# 04B-005.net
KiCad netlist of a schematic drawn in EAGLE
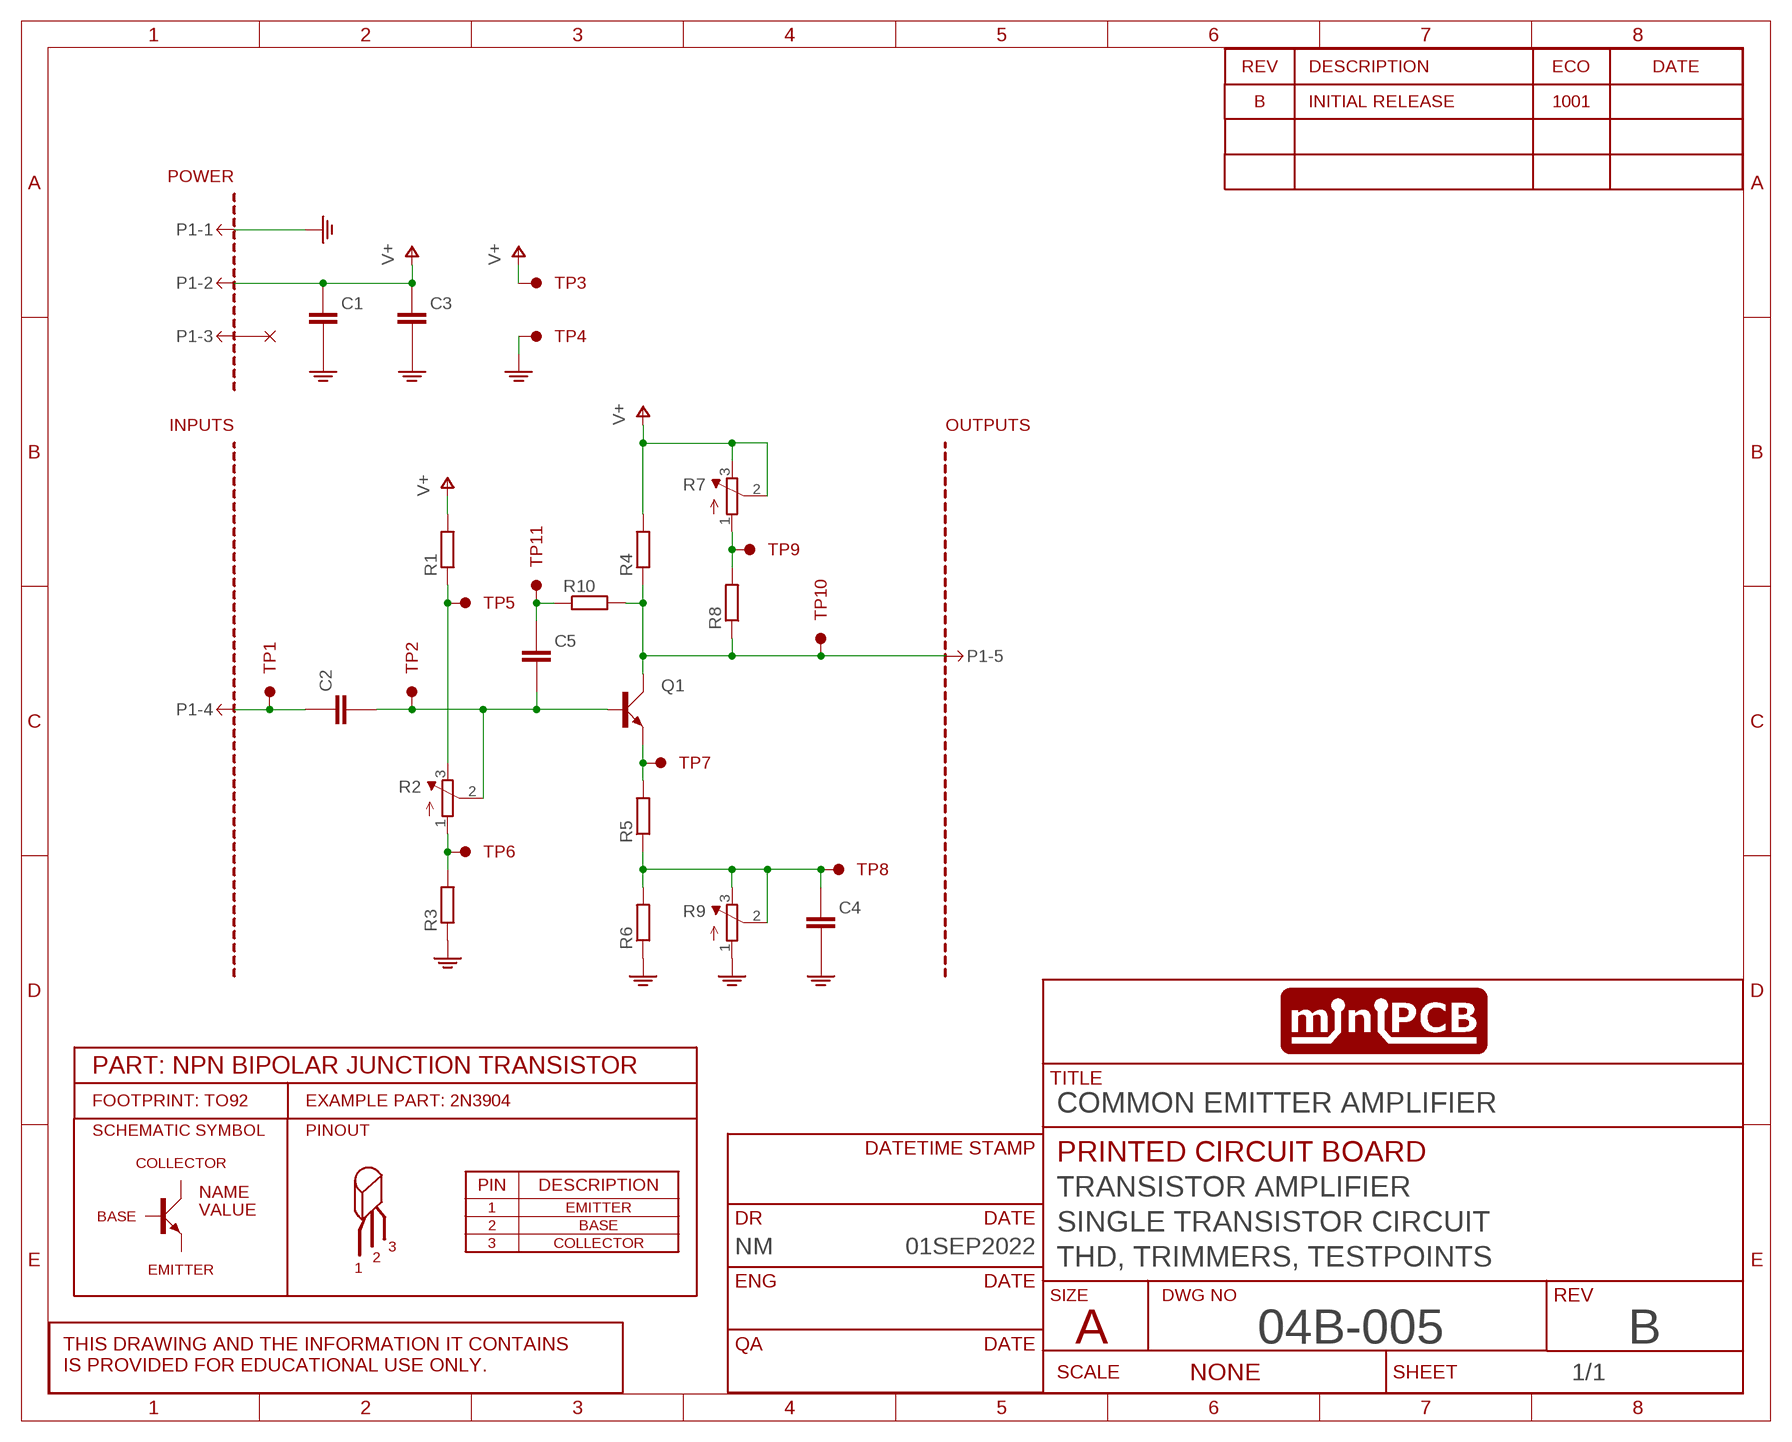
[diagram p0: schematic, sheet 1]

(export (version "E")
  (design (tool "Eeschema 10.0.6"))
  (components
    (comp (ref "C1")
      (value "CAPACITORTHD")
      (footprint "eagle-import:C050-024X044")
      (libsource (lib "eagle-import") (part "CAPACITORTHD"))
    )
    (comp (ref "C2")
      (value "CAPACITORTHD")
      (footprint "eagle-import:C050-024X044")
      (libsource (lib "eagle-import") (part "CAPACITORTHD"))
    )
    (comp (ref "C3")
      (value "CAPACITORTHD")
      (footprint "eagle-import:C050-024X044")
      (libsource (lib "eagle-import") (part "CAPACITORTHD"))
    )
    (comp (ref "C4")
      (value "CAPACITORTHD")
      (footprint "eagle-import:C050-024X044")
      (libsource (lib "eagle-import") (part "CAPACITORTHD"))
    )
    (comp (ref "C5")
      (value "CAPACITORTHD")
      (footprint "eagle-import:C050-024X044")
      (libsource (lib "eagle-import") (part "CAPACITORTHD"))
    )
    (comp (ref "P1-")
      (value "MINIPCB_5P50X50")
      (footprint "eagle-import:MINIPCB_5P_50X50MM")
      (fields (field (name "PART_NUMBER") "X04B-005-B"))
      (libsource (lib "eagle-import") (part "MINIPCB_5P50X50"))
    )
    (comp (ref "Q1")
      (value "BJT_NPNEBC")
      (footprint "eagle-import:TO92-EBC-OVAL")
      (libsource (lib "eagle-import") (part "BJT_NPNEBC"))
    )
    (comp (ref "R1")
      (value "RESISTOR10MM")
      (footprint "eagle-import:0207_10")
      (libsource (lib "eagle-import") (part "RESISTOR10MM"))
    )
    (comp (ref "R2")
      (value "TRIMPOT0.100THD")
      (footprint "eagle-import:TRIM_0100")
      (libsource (lib "eagle-import") (part "TRIMPOT0.100THD"))
    )
    (comp (ref "R3")
      (value "RESISTOR10MM")
      (footprint "eagle-import:0207_10")
      (libsource (lib "eagle-import") (part "RESISTOR10MM"))
    )
    (comp (ref "R4")
      (value "RESISTOR10MM")
      (footprint "eagle-import:0207_10")
      (libsource (lib "eagle-import") (part "RESISTOR10MM"))
    )
    (comp (ref "R5")
      (value "RESISTOR10MM")
      (footprint "eagle-import:0207_10")
      (libsource (lib "eagle-import") (part "RESISTOR10MM"))
    )
    (comp (ref "R6")
      (value "RESISTOR10MM")
      (footprint "eagle-import:0207_10")
      (libsource (lib "eagle-import") (part "RESISTOR10MM"))
    )
    (comp (ref "R7")
      (value "TRIMPOT0.100THD")
      (footprint "eagle-import:TRIM_0100")
      (libsource (lib "eagle-import") (part "TRIMPOT0.100THD"))
    )
    (comp (ref "R8")
      (value "RESISTOR10MM")
      (footprint "eagle-import:0207_10")
      (libsource (lib "eagle-import") (part "RESISTOR10MM"))
    )
    (comp (ref "R9")
      (value "TRIMPOT0.100THD")
      (footprint "eagle-import:TRIM_0100")
      (libsource (lib "eagle-import") (part "TRIMPOT0.100THD"))
    )
    (comp (ref "R10")
      (value "RESISTOR10MM")
      (footprint "eagle-import:0207_10")
      (libsource (lib "eagle-import") (part "RESISTOR10MM"))
    )
    (comp (ref "TP1")
      (value "TESTPOINTKE5000-SMTEXT")
      (footprint "eagle-import:PINS_1_TESTPOINT_KE5000_NOTEXT")
      (libsource (lib "eagle-import") (part "TESTPOINTKE5000-SMTEXT"))
    )
    (comp (ref "TP2")
      (value "TESTPOINTKE5000-SMTEXT")
      (footprint "eagle-import:PINS_1_TESTPOINT_KE5000_NOTEXT")
      (libsource (lib "eagle-import") (part "TESTPOINTKE5000-SMTEXT"))
    )
    (comp (ref "TP3")
      (value "TESTPOINTKE5000-SMTEXT")
      (footprint "eagle-import:PINS_1_TESTPOINT_KE5000_NOTEXT")
      (libsource (lib "eagle-import") (part "TESTPOINTKE5000-SMTEXT"))
    )
    (comp (ref "TP4")
      (value "TESTPOINTKE5000-SMTEXT")
      (footprint "eagle-import:PINS_1_TESTPOINT_KE5000_NOTEXT")
      (libsource (lib "eagle-import") (part "TESTPOINTKE5000-SMTEXT"))
    )
    (comp (ref "TP5")
      (value "TESTPOINTKE5000-SMTEXT")
      (footprint "eagle-import:PINS_1_TESTPOINT_KE5000_NOTEXT")
      (libsource (lib "eagle-import") (part "TESTPOINTKE5000-SMTEXT"))
    )
    (comp (ref "TP6")
      (value "TESTPOINTKE5000-SMTEXT")
      (footprint "eagle-import:PINS_1_TESTPOINT_KE5000_NOTEXT")
      (libsource (lib "eagle-import") (part "TESTPOINTKE5000-SMTEXT"))
    )
    (comp (ref "TP7")
      (value "TESTPOINTKE5000-SMTEXT")
      (footprint "eagle-import:PINS_1_TESTPOINT_KE5000_NOTEXT")
      (libsource (lib "eagle-import") (part "TESTPOINTKE5000-SMTEXT"))
    )
    (comp (ref "TP8")
      (value "TESTPOINTKE5000-SMTEXT")
      (footprint "eagle-import:PINS_1_TESTPOINT_KE5000_NOTEXT")
      (libsource (lib "eagle-import") (part "TESTPOINTKE5000-SMTEXT"))
    )
    (comp (ref "TP9")
      (value "TESTPOINTKE5000-SMTEXT")
      (footprint "eagle-import:PINS_1_TESTPOINT_KE5000_NOTEXT")
      (libsource (lib "eagle-import") (part "TESTPOINTKE5000-SMTEXT"))
    )
    (comp (ref "TP10")
      (value "TESTPOINTKE5000-SMTEXT")
      (footprint "eagle-import:PINS_1_TESTPOINT_KE5000_NOTEXT")
      (libsource (lib "eagle-import") (part "TESTPOINTKE5000-SMTEXT"))
    )
    (comp (ref "TP11")
      (value "TESTPOINTKE5000-SMTEXT")
      (footprint "eagle-import:PINS_1_TESTPOINT_KE5000_NOTEXT")
      (libsource (lib "eagle-import") (part "TESTPOINTKE5000-SMTEXT"))
    )
  )
  (nets
    (net (code "1") (name "GND") (class "Default")
      (node (ref "C1") (pin "2") (pinfunction "-_2") (pintype "passive"))
      (node (ref "C3") (pin "2") (pinfunction "-_2") (pintype "passive"))
      (node (ref "C4") (pin "2") (pinfunction "-_2") (pintype "passive"))
      (node (ref "P1-") (pin "1") (pinfunction "1_1") (pintype "bidirectional"))
      (node (ref "R3") (pin "1") (pinfunction "1_1") (pintype "passive"))
      (node (ref "R6") (pin "1") (pinfunction "1_1") (pintype "passive"))
      (node (ref "R9") (pin "1") (pinfunction "A_1") (pintype "passive"))
      (node (ref "TP4") (pin "1") (pinfunction "1_1") (pintype "bidirectional"))
    )
    (net (code "2") (name "Net-(C2-+)") (class "Default")
      (node (ref "C2") (pin "1") (pinfunction "+_1") (pintype "passive"))
      (node (ref "P1-") (pin "4") (pinfunction "1_4") (pintype "bidirectional"))
      (node (ref "TP1") (pin "1") (pinfunction "1_1") (pintype "bidirectional"))
    )
    (net (code "3") (name "Net-(C2--)") (class "Default")
      (node (ref "C2") (pin "2") (pinfunction "-_2") (pintype "passive"))
      (node (ref "C5") (pin "2") (pinfunction "-_2") (pintype "passive"))
      (node (ref "Q1") (pin "B") (pinfunction "B_B") (pintype "passive"))
      (node (ref "R2") (pin "2") (pinfunction "S_2") (pintype "passive"))
      (node (ref "TP2") (pin "1") (pinfunction "1_1") (pintype "bidirectional"))
    )
    (net (code "4") (name "Net-(C4-+)") (class "Default")
      (node (ref "C4") (pin "1") (pinfunction "+_1") (pintype "passive"))
      (node (ref "R5") (pin "1") (pinfunction "1_1") (pintype "passive"))
      (node (ref "R6") (pin "2") (pinfunction "2_2") (pintype "passive"))
      (node (ref "R9") (pin "2") (pinfunction "S_2") (pintype "passive"))
      (node (ref "R9") (pin "3") (pinfunction "E_3") (pintype "passive"))
      (node (ref "TP8") (pin "1") (pinfunction "1_1") (pintype "bidirectional"))
    )
    (net (code "5") (name "Net-(C5-+)") (class "Default")
      (node (ref "C5") (pin "1") (pinfunction "+_1") (pintype "passive"))
      (node (ref "R10") (pin "1") (pinfunction "1_1") (pintype "passive"))
      (node (ref "TP11") (pin "1") (pinfunction "1_1") (pintype "bidirectional"))
    )
    (net (code "6") (name "Net-(P1-H-1)") (class "Default")
      (node (ref "P1-") (pin "5") (pinfunction "1_5") (pintype "bidirectional"))
      (node (ref "Q1") (pin "C") (pinfunction "C_C") (pintype "passive"))
      (node (ref "R10") (pin "2") (pinfunction "2_2") (pintype "passive"))
      (node (ref "R4") (pin "1") (pinfunction "1_1") (pintype "passive"))
      (node (ref "R8") (pin "1") (pinfunction "1_1") (pintype "passive"))
      (node (ref "TP10") (pin "1") (pinfunction "1_1") (pintype "bidirectional"))
    )
    (net (code "7") (name "Net-(Q1-PadE)") (class "Default")
      (node (ref "Q1") (pin "E") (pinfunction "E_E") (pintype "passive"))
      (node (ref "R5") (pin "2") (pinfunction "2_2") (pintype "passive"))
      (node (ref "TP7") (pin "1") (pinfunction "1_1") (pintype "bidirectional"))
    )
    (net (code "8") (name "Net-(R2-A)") (class "Default")
      (node (ref "R2") (pin "1") (pinfunction "A_1") (pintype "passive"))
      (node (ref "R3") (pin "2") (pinfunction "2_2") (pintype "passive"))
      (node (ref "TP6") (pin "1") (pinfunction "1_1") (pintype "bidirectional"))
    )
    (net (code "9") (name "Net-(R2-E)") (class "Default")
      (node (ref "R1") (pin "1") (pinfunction "1_1") (pintype "passive"))
      (node (ref "R2") (pin "3") (pinfunction "E_3") (pintype "passive"))
      (node (ref "TP5") (pin "1") (pinfunction "1_1") (pintype "bidirectional"))
    )
    (net (code "10") (name "Net-(R7-A)") (class "Default")
      (node (ref "R7") (pin "1") (pinfunction "A_1") (pintype "passive"))
      (node (ref "R8") (pin "2") (pinfunction "2_2") (pintype "passive"))
      (node (ref "TP9") (pin "1") (pinfunction "1_1") (pintype "bidirectional"))
    )
    (net (code "11") (name "V+") (class "Default")
      (node (ref "C1") (pin "1") (pinfunction "+_1") (pintype "passive"))
      (node (ref "C3") (pin "1") (pinfunction "+_1") (pintype "passive"))
      (node (ref "P1-") (pin "2") (pinfunction "1_2") (pintype "bidirectional"))
      (node (ref "R1") (pin "2") (pinfunction "2_2") (pintype "passive"))
      (node (ref "R4") (pin "2") (pinfunction "2_2") (pintype "passive"))
      (node (ref "R7") (pin "2") (pinfunction "S_2") (pintype "passive"))
      (node (ref "R7") (pin "3") (pinfunction "E_3") (pintype "passive"))
      (node (ref "TP3") (pin "1") (pinfunction "1_1") (pintype "bidirectional"))
    )
    (net (code "12") (name "unconnected-(P1-C-1-Pad3)") (class "Default")
      (node (ref "P1-") (pin "3") (pinfunction "1_3") (pintype "bidirectional"))
    )
  )
)
